# Light_Detector_CCT.net
KiCad netlist of a schematic drawn in Altium Designer
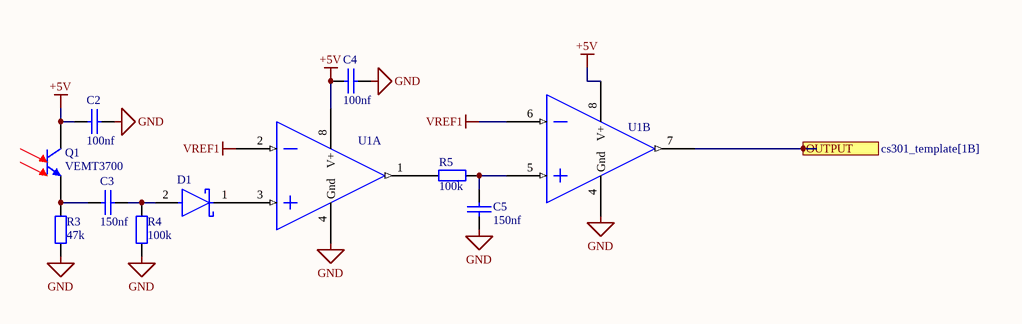
[diagram p0: Light Detector CCT.SchDoc]

(export (version "E")
  (design (tool "Eeschema 10.0.6"))
  (components
    (comp (ref "C2")
      (value "100nf")
      (footprint "0805 CAP")
      (description "SMT ceramic capacitor 0805 size")
      (libsource (lib "COMSYS301_2025") (part "CerCap_SMT_0805"))
    )
    (comp (ref "C3")
      (value "150nf")
      (footprint "0805 CAP")
      (description "SMT ceramic capacitor 0805 size")
      (libsource (lib "COMSYS301_2025") (part "CerCap_SMT_0805"))
    )
    (comp (ref "C4")
      (value "100nf")
      (footprint "0805 CAP")
      (description "SMT ceramic capacitor 0805 size")
      (libsource (lib "COMSYS301_2025") (part "CerCap_SMT_0805"))
    )
    (comp (ref "C5")
      (value "150nf")
      (footprint "0805 CAP")
      (description "SMT ceramic capacitor 0805 size")
      (libsource (lib "COMSYS301_2025") (part "CerCap_SMT_0805"))
    )
    (comp (ref "D1")
      (value "~")
      (footprint "FP-SOD68-MFG")
      (description "DIODE SCHOTTKY 30V 200MA DO34")
      (libsource (lib "Components - 23.08.25 - 03.47") (part "CMP-14398-000042-1"))
    )
    (comp (ref "Q1")
      (value "VEMT3700")
      (footprint "VEMT3700")
      (description "Silicon NPN Phototransistor")
      (libsource (lib "COMSYS301_2025") (part "VEMT3700"))
    )
    (comp (ref "R3")
      (value "47k")
      (footprint "0805 RES")
      (description "0805 resistor")
      (fields (field (name "PUBLISHER") "Altium Limited"))
      (libsource (lib "COMSYS301_2025") (part "Res_SMT_0805"))
    )
    (comp (ref "R4")
      (value "100k")
      (footprint "0805 RES")
      (description "0805 resistor")
      (fields (field (name "PUBLISHER") "Altium Limited"))
      (libsource (lib "COMSYS301_2025") (part "Res_SMT_0805"))
    )
    (comp (ref "R5")
      (value "100k")
      (footprint "0805 RES")
      (description "0805 resistor")
      (fields (field (name "PUBLISHER") "Altium Limited"))
      (libsource (lib "") (part "Res_SMT_0805_1"))
    )
    (comp (ref "U1")
      (value "TLC082")
      (footprint "ECE-SOIC8")
      (description "IC OPAMP TLC082 GP 10MHZ 8SOIC")
      (libsource (lib "EceParts") (part "TLC082"))
    )
  )
  (nets
    (net (code "1") (name "+5V") (class "Default")
      (node (ref "C2") (pin "1") (pinfunction "1_1") (pintype "passive"))
      (node (ref "C4") (pin "1") (pinfunction "1_1") (pintype "passive"))
      (node (ref "Q1") (pin "1") (pinfunction "C_1") (pintype "passive"))
      (node (ref "U1") (pin "8") (pinfunction "V+_8") (pintype "power_in"))
    )
    (net (code "2") (name "/OUTPUT") (class "Default")
      (node (ref "U1") (pin "7") (pinfunction "OUT2_7") (pintype "output"))
    )
    (net (code "3") (name "GND") (class "Default")
      (node (ref "C2") (pin "2") (pinfunction "2_2") (pintype "passive"))
      (node (ref "C4") (pin "2") (pinfunction "2_2") (pintype "passive"))
      (node (ref "C5") (pin "2") (pinfunction "2_2") (pintype "passive"))
      (node (ref "R3") (pin "1") (pinfunction "1_1") (pintype "passive"))
      (node (ref "R4") (pin "1") (pinfunction "1_1") (pintype "passive"))
      (node (ref "U1") (pin "4") (pinfunction "Gnd_4") (pintype "power_in"))
    )
    (net (code "4") (name "Net-(D1-A)") (class "Default")
      (node (ref "C3") (pin "2") (pinfunction "2_2") (pintype "passive"))
      (node (ref "D1") (pin "2") (pinfunction "A_2") (pintype "passive"))
      (node (ref "R4") (pin "2") (pinfunction "2_2") (pintype "passive"))
    )
    (net (code "5") (name "Net-(D1-C)") (class "Default")
      (node (ref "D1") (pin "1") (pinfunction "C_1") (pintype "passive"))
      (node (ref "U1") (pin "3") (pinfunction "IN1(+)_3") (pintype "input"))
    )
    (net (code "6") (name "Net-(Q1-E)") (class "Default")
      (node (ref "C3") (pin "1") (pinfunction "1_1") (pintype "passive"))
      (node (ref "Q1") (pin "2") (pinfunction "E_2") (pintype "passive"))
      (node (ref "R3") (pin "2") (pinfunction "2_2") (pintype "passive"))
    )
    (net (code "7") (name "Net-(U1A-OUT1)") (class "Default")
      (node (ref "R5") (pin "1") (pinfunction "1_1") (pintype "passive"))
      (node (ref "U1") (pin "1") (pinfunction "OUT1_1") (pintype "output"))
    )
    (net (code "8") (name "Net-(U1B-IN2(+))") (class "Default")
      (node (ref "C5") (pin "1") (pinfunction "1_1") (pintype "passive"))
      (node (ref "R5") (pin "2") (pinfunction "2_2") (pintype "passive"))
      (node (ref "U1") (pin "5") (pinfunction "IN2(+)_5") (pintype "input"))
    )
    (net (code "9") (name "VREF1") (class "Default")
      (node (ref "U1") (pin "2") (pinfunction "IN1(-)_2") (pintype "input"))
      (node (ref "U1") (pin "6") (pinfunction "IN2(-)_6") (pintype "input"))
    )
  )
)
